# NerfPWM.net
KiCad netlist of a schematic drawn in EAGLE
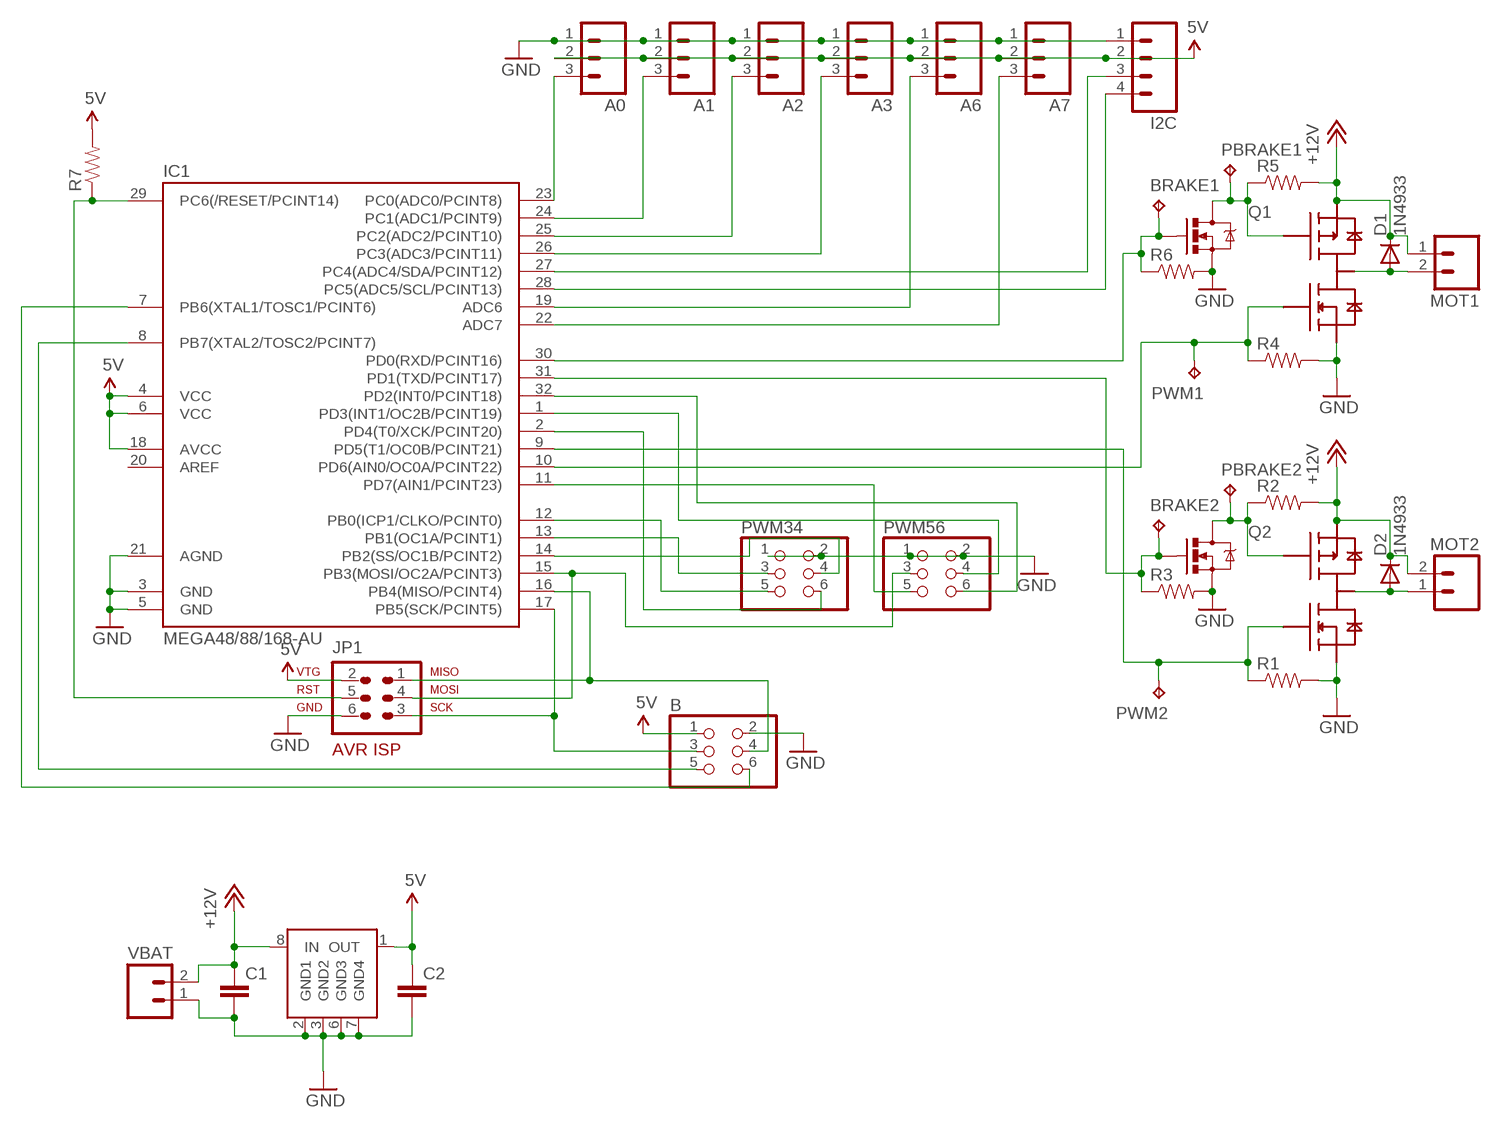
[diagram p0: schematic, sheet 1]

(export (version "E")
  (design (tool "Eeschema 10.0.6"))
  (components
    (comp (ref "A0")
      (value "M03PTH")
      (footprint "eagle-import:1X03")
      (libsource (lib "eagle-import") (part "M03PTH"))
    )
    (comp (ref "A1")
      (value "M03PTH")
      (footprint "eagle-import:1X03")
      (libsource (lib "eagle-import") (part "M03PTH"))
    )
    (comp (ref "A2")
      (value "M03PTH")
      (footprint "eagle-import:1X03")
      (libsource (lib "eagle-import") (part "M03PTH"))
    )
    (comp (ref "A3")
      (value "M03PTH")
      (footprint "eagle-import:1X03")
      (libsource (lib "eagle-import") (part "M03PTH"))
    )
    (comp (ref "A6")
      (value "M03PTH")
      (footprint "eagle-import:1X03")
      (libsource (lib "eagle-import") (part "M03PTH"))
    )
    (comp (ref "A7")
      (value "M03PTH")
      (footprint "eagle-import:1X03")
      (libsource (lib "eagle-import") (part "M03PTH"))
    )
    (comp (ref "B")
      (value "PINHD-2X3")
      (footprint "eagle-import:2X03")
      (libsource (lib "eagle-import") (part "PINHD-2X3"))
    )
    (comp (ref "BRAKE1")
      (value "TPTP10R")
      (footprint "eagle-import:TP10R")
      (libsource (lib "eagle-import") (part "TPTP10R"))
    )
    (comp (ref "BRAKE2")
      (value "TPTP10R")
      (footprint "eagle-import:TP10R")
      (libsource (lib "eagle-import") (part "TPTP10R"))
    )
    (comp (ref "C1")
      (value "CAP1206")
      (footprint "eagle-import:1206")
      (libsource (lib "eagle-import") (part "CAP1206"))
    )
    (comp (ref "C2")
      (value "CAP1206")
      (footprint "eagle-import:1206")
      (libsource (lib "eagle-import") (part "CAP1206"))
    )
    (comp (ref "D1")
      (value "1N4933")
      (footprint "eagle-import:DO41-10")
      (libsource (lib "eagle-import") (part "1N4933"))
    )
    (comp (ref "D2")
      (value "1N4933")
      (footprint "eagle-import:DO41-10")
      (libsource (lib "eagle-import") (part "1N4933"))
    )
    (comp (ref "I2C")
      (value "M04PTH")
      (footprint "eagle-import:1X04")
      (libsource (lib "eagle-import") (part "M04PTH"))
    )
    (comp (ref "IC1")
      (value "MEGA48/88/168-AU")
      (footprint "eagle-import:TQFP32-08")
      (libsource (lib "eagle-import") (part "MEGA48/88/168-AU"))
    )
    (comp (ref "JP1")
      (value "AVR-ISP-6")
      (footprint "eagle-import:AVR-ISP-6")
      (libsource (lib "eagle-import") (part "AVR-ISP-6"))
    )
    (comp (ref "MOT1")
      (value "M023.5MM_LOCK")
      (footprint "eagle-import:SCREWTERMINAL-3.5MM-2_LOCK")
      (libsource (lib "eagle-import") (part "M023.5MM_LOCK"))
    )
    (comp (ref "MOT2")
      (value "M023.5MM_LOCK")
      (footprint "eagle-import:SCREWTERMINAL-3.5MM-2_LOCK")
      (libsource (lib "eagle-import") (part "M023.5MM_LOCK"))
    )
    (comp (ref "PBRAKE1")
      (value "TPTP10R")
      (footprint "eagle-import:TP10R")
      (libsource (lib "eagle-import") (part "TPTP10R"))
    )
    (comp (ref "PBRAKE2")
      (value "TPTP10R")
      (footprint "eagle-import:TP10R")
      (libsource (lib "eagle-import") (part "TPTP10R"))
    )
    (comp (ref "PWM1")
      (value "TPTP10R")
      (footprint "eagle-import:TP10R")
      (libsource (lib "eagle-import") (part "TPTP10R"))
    )
    (comp (ref "PWM2")
      (value "TPTP10R")
      (footprint "eagle-import:TP10R")
      (libsource (lib "eagle-import") (part "TPTP10R"))
    )
    (comp (ref "PWM34")
      (value "PINHD-2X3")
      (footprint "eagle-import:2X03")
      (libsource (lib "eagle-import") (part "PINHD-2X3"))
    )
    (comp (ref "PWM56")
      (value "PINHD-2X3")
      (footprint "eagle-import:2X03")
      (libsource (lib "eagle-import") (part "PINHD-2X3"))
    )
    (comp (ref "Q1")
      (value "MOSFET-NCHANNELSMD")
      (footprint "eagle-import:SOT23-3")
      (libsource (lib "eagle-import") (part "MOSFET-NCHANNELSMD"))
    )
    (comp (ref "Q2")
      (value "MOSFET-NCHANNELSMD")
      (footprint "eagle-import:SOT23-3")
      (libsource (lib "eagle-import") (part "MOSFET-NCHANNELSMD"))
    )
    (comp (ref "R1")
      (value "RESISTOR")
      (footprint "eagle-import:0805")
      (libsource (lib "eagle-import") (part "RESISTOR"))
    )
    (comp (ref "R2")
      (value "RESISTOR")
      (footprint "eagle-import:0805")
      (libsource (lib "eagle-import") (part "RESISTOR"))
    )
    (comp (ref "R3")
      (value "RESISTOR")
      (footprint "eagle-import:0805")
      (libsource (lib "eagle-import") (part "RESISTOR"))
    )
    (comp (ref "R4")
      (value "RESISTOR")
      (footprint "eagle-import:0805")
      (libsource (lib "eagle-import") (part "RESISTOR"))
    )
    (comp (ref "R5")
      (value "RESISTOR")
      (footprint "eagle-import:0805")
      (libsource (lib "eagle-import") (part "RESISTOR"))
    )
    (comp (ref "R6")
      (value "RESISTOR")
      (footprint "eagle-import:0805")
      (libsource (lib "eagle-import") (part "RESISTOR"))
    )
    (comp (ref "R7")
      (value "RESISTOR")
      (footprint "eagle-import:0805")
      (libsource (lib "eagle-import") (part "RESISTOR"))
    )
    (comp (ref "U$3")
      (value "MC78L00AD")
      (footprint "eagle-import:SOIC8")
      (libsource (lib "eagle-import") (part "MC78L00AD"))
    )
    (comp (ref "U$4")
      (value "SI4501BDY")
      (footprint "eagle-import:SOIC8")
      (libsource (lib "eagle-import") (part "SI4501BDY"))
    )
    (comp (ref "U$5")
      (value "SI4501BDY")
      (footprint "eagle-import:SOIC8")
      (libsource (lib "eagle-import") (part "SI4501BDY"))
    )
    (comp (ref "VBAT")
      (value "M023.5MM_LOCK")
      (footprint "eagle-import:SCREWTERMINAL-3.5MM-2_LOCK")
      (libsource (lib "eagle-import") (part "M023.5MM_LOCK"))
    )
  )
  (nets
    (net (code "1") (name "+12V") (class "Default")
      (node (ref "C1") (pin "1") (pinfunction "1_1") (pintype "passive"))
      (node (ref "D1") (pin "C") (pinfunction "C_C") (pintype "passive"))
      (node (ref "D2") (pin "C") (pinfunction "C_C") (pintype "passive"))
      (node (ref "MOT1") (pin "1") (pinfunction "1_1") (pintype "passive"))
      (node (ref "MOT2") (pin "2") (pinfunction "2_2") (pintype "passive"))
      (node (ref "R2") (pin "2") (pinfunction "2_2") (pintype "passive"))
      (node (ref "R5") (pin "2") (pinfunction "2_2") (pintype "passive"))
      (node (ref "U$3") (pin "8") (pinfunction "IN_8") (pintype "power_in"))
      (node (ref "U$4") (pin "3") (pinfunction "S2_3") (pintype "power_in"))
      (node (ref "U$5") (pin "3") (pinfunction "S2_3") (pintype "power_in"))
      (node (ref "VBAT") (pin "2") (pinfunction "2_2") (pintype "passive"))
    )
    (net (code "2") (name "5V") (class "Default")
      (node (ref "A0") (pin "2") (pinfunction "2_2") (pintype "passive"))
      (node (ref "A1") (pin "2") (pinfunction "2_2") (pintype "passive"))
      (node (ref "A2") (pin "2") (pinfunction "2_2") (pintype "passive"))
      (node (ref "A3") (pin "2") (pinfunction "2_2") (pintype "passive"))
      (node (ref "A6") (pin "2") (pinfunction "2_2") (pintype "passive"))
      (node (ref "A7") (pin "2") (pinfunction "2_2") (pintype "passive"))
      (node (ref "B") (pin "1") (pinfunction "1_1") (pintype "passive"))
      (node (ref "C2") (pin "1") (pinfunction "1_1") (pintype "passive"))
      (node (ref "I2C") (pin "2") (pinfunction "2_2") (pintype "passive"))
      (node (ref "IC1") (pin "18") (pinfunction "AVCC_18") (pintype "passive"))
      (node (ref "IC1") (pin "4") (pinfunction "VCC_4") (pintype "power_in"))
      (node (ref "IC1") (pin "6") (pinfunction "VCC_6") (pintype "power_in"))
      (node (ref "JP1") (pin "2") (pinfunction "2_2") (pintype "passive"))
      (node (ref "R7") (pin "2") (pinfunction "2_2") (pintype "passive"))
      (node (ref "U$3") (pin "1") (pinfunction "OUT_1") (pintype "power_in"))
    )
    (net (code "3") (name "GND") (class "Default")
      (node (ref "A0") (pin "1") (pinfunction "1_1") (pintype "passive"))
      (node (ref "A1") (pin "1") (pinfunction "1_1") (pintype "passive"))
      (node (ref "A2") (pin "1") (pinfunction "1_1") (pintype "passive"))
      (node (ref "A3") (pin "1") (pinfunction "1_1") (pintype "passive"))
      (node (ref "A6") (pin "1") (pinfunction "1_1") (pintype "passive"))
      (node (ref "A7") (pin "1") (pinfunction "1_1") (pintype "passive"))
      (node (ref "B") (pin "2") (pinfunction "2_2") (pintype "passive"))
      (node (ref "C1") (pin "2") (pinfunction "2_2") (pintype "passive"))
      (node (ref "C2") (pin "2") (pinfunction "2_2") (pintype "passive"))
      (node (ref "I2C") (pin "1") (pinfunction "1_1") (pintype "passive"))
      (node (ref "IC1") (pin "21") (pinfunction "AGND_21") (pintype "power_in"))
      (node (ref "IC1") (pin "3") (pinfunction "GND_3") (pintype "power_in"))
      (node (ref "IC1") (pin "5") (pinfunction "GND_5") (pintype "power_in"))
      (node (ref "JP1") (pin "6") (pinfunction "6_6") (pintype "passive"))
      (node (ref "PWM34") (pin "1") (pinfunction "1_1") (pintype "passive"))
      (node (ref "PWM34") (pin "2") (pinfunction "2_2") (pintype "passive"))
      (node (ref "PWM56") (pin "1") (pinfunction "1_1") (pintype "passive"))
      (node (ref "PWM56") (pin "2") (pinfunction "2_2") (pintype "passive"))
      (node (ref "Q1") (pin "2") (pinfunction "S_2") (pintype "passive"))
      (node (ref "Q2") (pin "2") (pinfunction "S_2") (pintype "passive"))
      (node (ref "R1") (pin "2") (pinfunction "2_2") (pintype "passive"))
      (node (ref "R3") (pin "2") (pinfunction "2_2") (pintype "passive"))
      (node (ref "R4") (pin "2") (pinfunction "2_2") (pintype "passive"))
      (node (ref "R6") (pin "2") (pinfunction "2_2") (pintype "passive"))
      (node (ref "U$3") (pin "2") (pinfunction "GND1_2") (pintype "power_in"))
      (node (ref "U$3") (pin "3") (pinfunction "GND2_3") (pintype "power_in"))
      (node (ref "U$3") (pin "6") (pinfunction "GND3_6") (pintype "power_in"))
      (node (ref "U$3") (pin "7") (pinfunction "GND4_7") (pintype "power_in"))
      (node (ref "U$4") (pin "1") (pinfunction "S1_1") (pintype "power_in"))
      (node (ref "U$5") (pin "1") (pinfunction "S1_1") (pintype "power_in"))
      (node (ref "VBAT") (pin "1") (pinfunction "1_1") (pintype "passive"))
    )
    (net (code "4") (name "Net-(D1-PadA)") (class "Default")
      (node (ref "D1") (pin "A") (pinfunction "A_A") (pintype "passive"))
      (node (ref "MOT1") (pin "2") (pinfunction "2_2") (pintype "passive"))
      (node (ref "U$4") (pin "5") (pinfunction "D_5") (pintype "output"))
      (node (ref "U$4") (pin "6") (pinfunction "D_6") (pintype "output"))
      (node (ref "U$4") (pin "7") (pinfunction "D_7") (pintype "output"))
      (node (ref "U$4") (pin "8") (pinfunction "D_8") (pintype "output"))
    )
    (net (code "5") (name "Net-(D2-PadA)") (class "Default")
      (node (ref "D2") (pin "A") (pinfunction "A_A") (pintype "passive"))
      (node (ref "MOT2") (pin "1") (pinfunction "1_1") (pintype "passive"))
      (node (ref "U$5") (pin "5") (pinfunction "D_5") (pintype "output"))
      (node (ref "U$5") (pin "6") (pinfunction "D_6") (pintype "output"))
      (node (ref "U$5") (pin "7") (pinfunction "D_7") (pintype "output"))
      (node (ref "U$5") (pin "8") (pinfunction "D_8") (pintype "output"))
    )
    (net (code "6") (name "Net-(IC1-ADC6)") (class "Default")
      (node (ref "A6") (pin "3") (pinfunction "3_3") (pintype "passive"))
      (node (ref "IC1") (pin "19") (pinfunction "ADC6_19") (pintype "passive"))
    )
    (net (code "7") (name "Net-(IC1-ADC7)") (class "Default")
      (node (ref "A7") (pin "3") (pinfunction "3_3") (pintype "passive"))
      (node (ref "IC1") (pin "22") (pinfunction "ADC7_22") (pintype "passive"))
    )
    (net (code "8") (name "Net-(IC1-PB0(ICP1{slash}CLKO{slash}PCINT0))") (class "Default")
      (node (ref "IC1") (pin "12") (pinfunction "PB0(ICP1/CLKO/PCINT0)_12") (pintype "bidirectional"))
      (node (ref "PWM34") (pin "5") (pinfunction "5_5") (pintype "passive"))
    )
    (net (code "9") (name "Net-(IC1-PB1(OC1A{slash}PCINT1))") (class "Default")
      (node (ref "IC1") (pin "13") (pinfunction "PB1(OC1A/PCINT1)_13") (pintype "bidirectional"))
      (node (ref "PWM34") (pin "3") (pinfunction "3_3") (pintype "passive"))
    )
    (net (code "10") (name "Net-(IC1-PB2(SS{slash}OC1B{slash}PCINT2))") (class "Default")
      (node (ref "IC1") (pin "14") (pinfunction "PB2(SS/OC1B/PCINT2)_14") (pintype "bidirectional"))
      (node (ref "PWM34") (pin "4") (pinfunction "4_4") (pintype "passive"))
    )
    (net (code "11") (name "Net-(IC1-PB3(MOSI{slash}OC2A{slash}PCINT3))") (class "Default")
      (node (ref "IC1") (pin "15") (pinfunction "PB3(MOSI/OC2A/PCINT3)_15") (pintype "bidirectional"))
      (node (ref "JP1") (pin "4") (pinfunction "4_4") (pintype "passive"))
      (node (ref "PWM56") (pin "3") (pinfunction "3_3") (pintype "passive"))
    )
    (net (code "12") (name "Net-(IC1-PB4(MISO{slash}PCINT4))") (class "Default")
      (node (ref "B") (pin "4") (pinfunction "4_4") (pintype "passive"))
      (node (ref "IC1") (pin "16") (pinfunction "PB4(MISO/PCINT4)_16") (pintype "bidirectional"))
      (node (ref "JP1") (pin "1") (pinfunction "1_1") (pintype "passive"))
    )
    (net (code "13") (name "Net-(IC1-PB5(SCK{slash}PCINT5))") (class "Default")
      (node (ref "B") (pin "3") (pinfunction "3_3") (pintype "passive"))
      (node (ref "IC1") (pin "17") (pinfunction "PB5(SCK/PCINT5)_17") (pintype "bidirectional"))
      (node (ref "JP1") (pin "3") (pinfunction "3_3") (pintype "passive"))
    )
    (net (code "14") (name "Net-(IC1-PB6(XTAL1{slash}TOSC1{slash}PCINT6))") (class "Default")
      (node (ref "B") (pin "6") (pinfunction "6_6") (pintype "passive"))
      (node (ref "IC1") (pin "7") (pinfunction "PB6(XTAL1/TOSC1/PCINT6)_7") (pintype "bidirectional"))
    )
    (net (code "15") (name "Net-(IC1-PB7(XTAL2{slash}TOSC2{slash}PCINT7))") (class "Default")
      (node (ref "B") (pin "5") (pinfunction "5_5") (pintype "passive"))
      (node (ref "IC1") (pin "8") (pinfunction "PB7(XTAL2/TOSC2/PCINT7)_8") (pintype "bidirectional"))
    )
    (net (code "16") (name "Net-(IC1-PC0(ADC0{slash}PCINT8))") (class "Default")
      (node (ref "A0") (pin "3") (pinfunction "3_3") (pintype "passive"))
      (node (ref "IC1") (pin "23") (pinfunction "PC0(ADC0/PCINT8)_23") (pintype "bidirectional"))
    )
    (net (code "17") (name "Net-(IC1-PC1(ADC1{slash}PCINT9))") (class "Default")
      (node (ref "A1") (pin "3") (pinfunction "3_3") (pintype "passive"))
      (node (ref "IC1") (pin "24") (pinfunction "PC1(ADC1/PCINT9)_24") (pintype "bidirectional"))
    )
    (net (code "18") (name "Net-(IC1-PC2(ADC2{slash}PCINT10))") (class "Default")
      (node (ref "A2") (pin "3") (pinfunction "3_3") (pintype "passive"))
      (node (ref "IC1") (pin "25") (pinfunction "PC2(ADC2/PCINT10)_25") (pintype "bidirectional"))
    )
    (net (code "19") (name "Net-(IC1-PC3(ADC3{slash}PCINT11))") (class "Default")
      (node (ref "A3") (pin "3") (pinfunction "3_3") (pintype "passive"))
      (node (ref "IC1") (pin "26") (pinfunction "PC3(ADC3/PCINT11)_26") (pintype "bidirectional"))
    )
    (net (code "20") (name "Net-(IC1-PC4(ADC4{slash}SDA{slash}PCINT12))") (class "Default")
      (node (ref "I2C") (pin "3") (pinfunction "3_3") (pintype "passive"))
      (node (ref "IC1") (pin "27") (pinfunction "PC4(ADC4/SDA/PCINT12)_27") (pintype "bidirectional"))
    )
    (net (code "21") (name "Net-(IC1-PC5(ADC5{slash}SCL{slash}PCINT13))") (class "Default")
      (node (ref "I2C") (pin "4") (pinfunction "4_4") (pintype "passive"))
      (node (ref "IC1") (pin "28") (pinfunction "PC5(ADC5/SCL/PCINT13)_28") (pintype "bidirectional"))
    )
    (net (code "22") (name "Net-(IC1-PC6({slash}RESET{slash}PCINT14))") (class "Default")
      (node (ref "IC1") (pin "29") (pinfunction "PC6(/RESET/PCINT14)_29") (pintype "bidirectional"))
      (node (ref "JP1") (pin "5") (pinfunction "5_5") (pintype "passive"))
      (node (ref "R7") (pin "1") (pinfunction "1_1") (pintype "passive"))
    )
    (net (code "23") (name "Net-(IC1-PD0(RXD{slash}PCINT16))") (class "Default")
      (node (ref "BRAKE1") (pin "TP") (pinfunction "TP_TP") (pintype "input"))
      (node (ref "IC1") (pin "30") (pinfunction "PD0(RXD/PCINT16)_30") (pintype "bidirectional"))
      (node (ref "Q1") (pin "1") (pinfunction "G_1") (pintype "passive"))
      (node (ref "R6") (pin "1") (pinfunction "1_1") (pintype "passive"))
    )
    (net (code "24") (name "Net-(IC1-PD1(TXD{slash}PCINT17))") (class "Default")
      (node (ref "BRAKE2") (pin "TP") (pinfunction "TP_TP") (pintype "input"))
      (node (ref "IC1") (pin "31") (pinfunction "PD1(TXD/PCINT17)_31") (pintype "bidirectional"))
      (node (ref "Q2") (pin "1") (pinfunction "G_1") (pintype "passive"))
      (node (ref "R3") (pin "1") (pinfunction "1_1") (pintype "passive"))
    )
    (net (code "25") (name "Net-(IC1-PD2(INT0{slash}PCINT18))") (class "Default")
      (node (ref "IC1") (pin "32") (pinfunction "PD2(INT0/PCINT18)_32") (pintype "bidirectional"))
      (node (ref "PWM56") (pin "6") (pinfunction "6_6") (pintype "passive"))
    )
    (net (code "26") (name "Net-(IC1-PD3(INT1{slash}OC2B{slash}PCINT19))") (class "Default")
      (node (ref "IC1") (pin "1") (pinfunction "PD3(INT1/OC2B/PCINT19)_1") (pintype "bidirectional"))
      (node (ref "PWM56") (pin "4") (pinfunction "4_4") (pintype "passive"))
    )
    (net (code "27") (name "Net-(IC1-PD4(T0{slash}XCK{slash}PCINT20))") (class "Default")
      (node (ref "IC1") (pin "2") (pinfunction "PD4(T0/XCK/PCINT20)_2") (pintype "bidirectional"))
      (node (ref "PWM34") (pin "6") (pinfunction "6_6") (pintype "passive"))
    )
    (net (code "28") (name "Net-(IC1-PD5(T1{slash}OC0B{slash}PCINT21))") (class "Default")
      (node (ref "IC1") (pin "9") (pinfunction "PD5(T1/OC0B/PCINT21)_9") (pintype "bidirectional"))
      (node (ref "PWM2") (pin "TP") (pinfunction "TP_TP") (pintype "input"))
      (node (ref "R1") (pin "1") (pinfunction "1_1") (pintype "passive"))
      (node (ref "U$5") (pin "2") (pinfunction "G1_2") (pintype "input"))
    )
    (net (code "29") (name "Net-(IC1-PD6(AIN0{slash}OC0A{slash}PCINT22))") (class "Default")
      (node (ref "IC1") (pin "10") (pinfunction "PD6(AIN0/OC0A/PCINT22)_10") (pintype "bidirectional"))
      (node (ref "PWM1") (pin "TP") (pinfunction "TP_TP") (pintype "input"))
      (node (ref "R4") (pin "1") (pinfunction "1_1") (pintype "passive"))
      (node (ref "U$4") (pin "2") (pinfunction "G1_2") (pintype "input"))
    )
    (net (code "30") (name "Net-(IC1-PD7(AIN1{slash}PCINT23))") (class "Default")
      (node (ref "IC1") (pin "11") (pinfunction "PD7(AIN1/PCINT23)_11") (pintype "bidirectional"))
      (node (ref "PWM56") (pin "5") (pinfunction "5_5") (pintype "passive"))
    )
    (net (code "31") (name "Net-(Q1-D)") (class "Default")
      (node (ref "PBRAKE1") (pin "TP") (pinfunction "TP_TP") (pintype "input"))
      (node (ref "Q1") (pin "3") (pinfunction "D_3") (pintype "passive"))
      (node (ref "R5") (pin "1") (pinfunction "1_1") (pintype "passive"))
      (node (ref "U$4") (pin "4") (pinfunction "G2_4") (pintype "input"))
    )
    (net (code "32") (name "Net-(Q2-D)") (class "Default")
      (node (ref "PBRAKE2") (pin "TP") (pinfunction "TP_TP") (pintype "input"))
      (node (ref "Q2") (pin "3") (pinfunction "D_3") (pintype "passive"))
      (node (ref "R2") (pin "1") (pinfunction "1_1") (pintype "passive"))
      (node (ref "U$5") (pin "4") (pinfunction "G2_4") (pintype "input"))
    )
    (net (code "33") (name "unconnected-(IC1-AREF-Pad20)") (class "Default")
      (node (ref "IC1") (pin "20") (pinfunction "AREF_20") (pintype "passive"))
    )
  )
)
